# Sheet1.net
KiCad netlist of a schematic drawn in Altium Designer
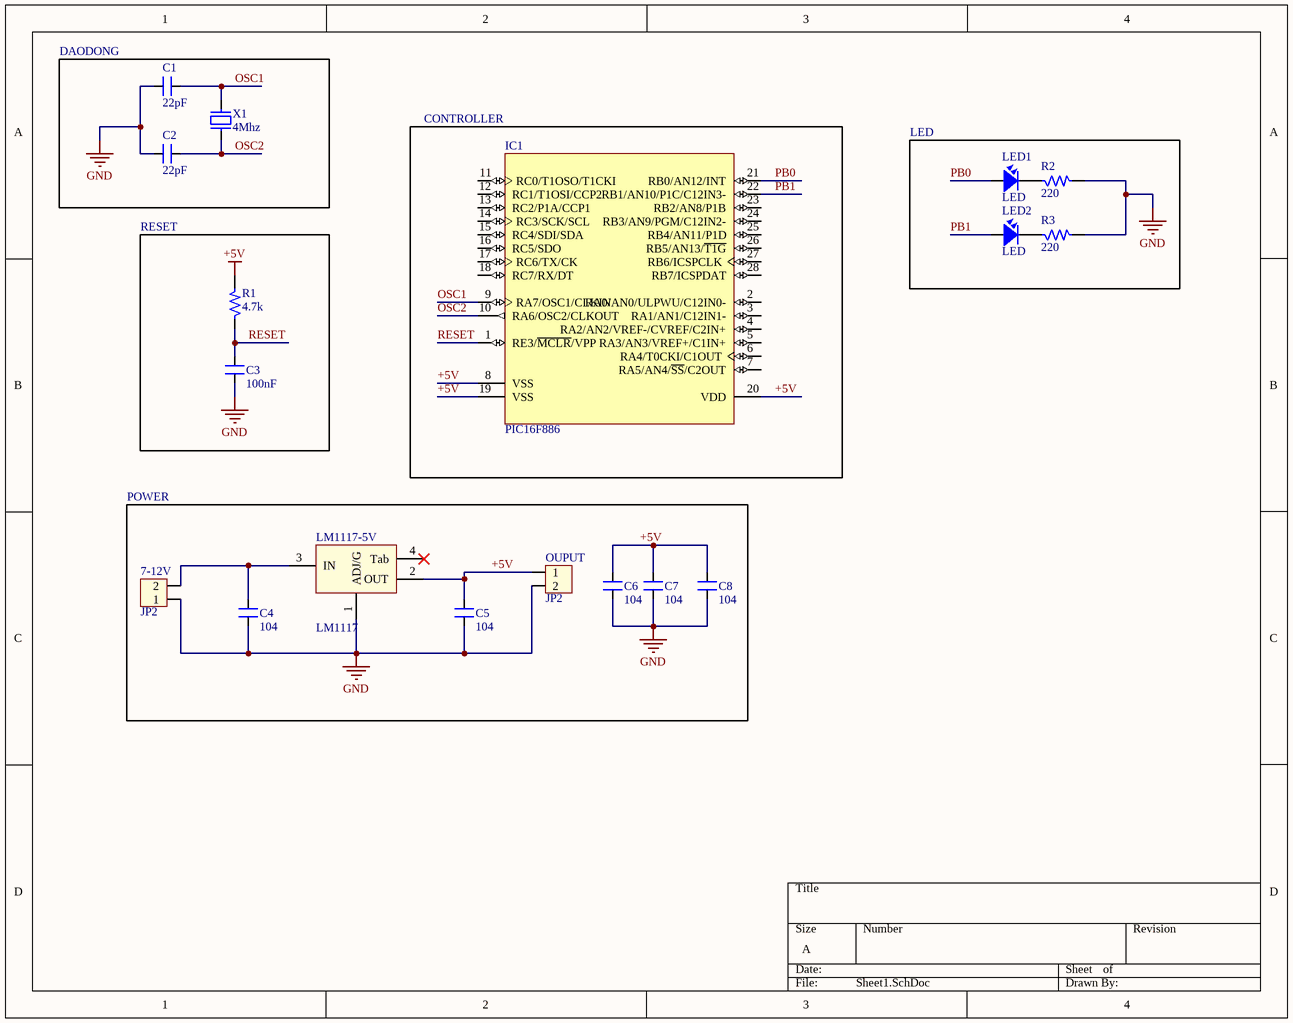
[diagram p0: Sheet1.SchDoc]

(export (version "E")
  (design (tool "Eeschema 10.0.6"))
  (components
    (comp (ref "7-12V")
      (value "JP2")
      (footprint "CON2")
      (description "Connector 2")
      (libsource (lib "syhaunguyen") (part "Con2"))
    )
    (comp (ref "C1")
      (value "22pF")
      (footprint "CN1")
      (description "Cap np  1pF - 472pF")
      (libsource (lib "syhaunguyen") (part "CN1"))
    )
    (comp (ref "C2")
      (value "22pF")
      (footprint "CN1")
      (description "Cap np  1pF - 472pF")
      (libsource (lib "syhaunguyen") (part "CN1"))
    )
    (comp (ref "C3")
      (value "100nF")
      (footprint "SM-0805")
      (description "Cap SMD")
      (libsource (lib "syhaunguyen") (part "CM"))
    )
    (comp (ref "C4")
      (value "104")
      (footprint "SM-0805")
      (description "Cap SMD")
      (libsource (lib "syhaunguyen") (part "CM"))
    )
    (comp (ref "C5")
      (value "104")
      (footprint "SM-0805")
      (description "Cap SMD")
      (libsource (lib "syhaunguyen") (part "CM"))
    )
    (comp (ref "C6")
      (value "104")
      (footprint "CN4")
      (description "Cap np W0.4")
      (libsource (lib "syhaunguyen") (part "CN4"))
    )
    (comp (ref "C7")
      (value "104")
      (footprint "CN4")
      (description "Cap np W0.4")
      (libsource (lib "syhaunguyen") (part "CN4"))
    )
    (comp (ref "C8")
      (value "104")
      (footprint "CN4")
      (description "Cap np W0.4")
      (libsource (lib "syhaunguyen") (part "CN4"))
    )
    (comp (ref "IC1")
      (value "PIC16F886")
      (footprint "DIP28/W0.3")
      (libsource (lib "syhaunguyen") (part "PIC16F886"))
    )
    (comp (ref "LED1")
      (value "LED")
      (footprint "LED-3")
      (description "LED Single colour Green and Red")
      (libsource (lib "syhaunguyen") (part "LED"))
    )
    (comp (ref "LED2")
      (value "LED")
      (footprint "LED-3")
      (description "LED Single colour Green and Red")
      (libsource (lib "syhaunguyen") (part "LED"))
    )
    (comp (ref "LM1117-5V")
      (value "LM1117")
      (footprint "SOT223-4N")
      (description "3v3")
      (libsource (lib "syhaunguyen") (part "LM1117"))
    )
    (comp (ref "OUPUT")
      (value "JP2")
      (footprint "CON2")
      (description "Connector 2")
      (libsource (lib "") (part "Con2_1"))
    )
    (comp (ref "R1")
      (value "4.7k")
      (footprint "R1/4W")
      (description "Resistor 1/4W")
      (libsource (lib "syhaunguyen") (part "R"))
    )
    (comp (ref "R2")
      (value "220")
      (footprint "R1/4W")
      (description "Resistor 1/4W")
      (libsource (lib "syhaunguyen") (part "R"))
    )
    (comp (ref "R3")
      (value "220")
      (footprint "R1/4W")
      (description "Resistor 1/4W")
      (libsource (lib "syhaunguyen") (part "R"))
    )
    (comp (ref "X1")
      (value "4Mhz")
      (footprint "XT2")
      (description "Crystal For all Crystal 2pin.")
      (libsource (lib "syhaunguyen") (part "XT2"))
    )
  )
  (nets
    (net (code "1") (name "+5V") (class "Default")
      (node (ref "C5") (pin "2") (pinfunction "2_2") (pintype "passive"))
      (node (ref "C6") (pin "2") (pinfunction "2_2") (pintype "passive"))
      (node (ref "C7") (pin "2") (pinfunction "2_2") (pintype "passive"))
      (node (ref "C8") (pin "2") (pinfunction "2_2") (pintype "passive"))
      (node (ref "IC1") (pin "19") (pinfunction "VSS_19") (pintype "power_in"))
      (node (ref "IC1") (pin "20") (pinfunction "VDD_20") (pintype "power_in"))
      (node (ref "IC1") (pin "8") (pinfunction "VSS_8") (pintype "power_in"))
      (node (ref "LM1117-5V") (pin "2") (pinfunction "OUT_2") (pintype "passive"))
      (node (ref "OUPUT") (pin "1") (pinfunction "1_1") (pintype "passive"))
      (node (ref "R1") (pin "2") (pinfunction "2_2") (pintype "passive"))
    )
    (net (code "2") (name "/OSC1") (class "Default")
      (node (ref "C1") (pin "2") (pinfunction "2_2") (pintype "passive"))
      (node (ref "IC1") (pin "9") (pinfunction "RA7/OSC1/CLKIN_9") (pintype "bidirectional"))
      (node (ref "X1") (pin "1") (pinfunction "1_1") (pintype "passive"))
    )
    (net (code "3") (name "/OSC2") (class "Default")
      (node (ref "C2") (pin "2") (pinfunction "2_2") (pintype "passive"))
      (node (ref "IC1") (pin "10") (pinfunction "RA6/OSC2/CLKOUT_10") (pintype "output"))
      (node (ref "X1") (pin "2") (pinfunction "2_2") (pintype "passive"))
    )
    (net (code "4") (name "/PB0") (class "Default")
      (node (ref "IC1") (pin "21") (pinfunction "RB0/AN12/INT_21") (pintype "bidirectional"))
      (node (ref "LED1") (pin "1") (pinfunction "1_1") (pintype "passive"))
    )
    (net (code "5") (name "/PB1") (class "Default")
      (node (ref "IC1") (pin "22") (pinfunction "RB1/AN10/P1C/C12IN3-_22") (pintype "bidirectional"))
      (node (ref "LED2") (pin "1") (pinfunction "1_1") (pintype "passive"))
    )
    (net (code "6") (name "/RESET") (class "Default")
      (node (ref "C3") (pin "2") (pinfunction "2_2") (pintype "passive"))
      (node (ref "IC1") (pin "1") (pinfunction "RE3/~{MCLR}/VPP_1") (pintype "bidirectional"))
      (node (ref "R1") (pin "1") (pinfunction "1_1") (pintype "passive"))
    )
    (net (code "7") (name "GND") (class "Default")
      (node (ref "7-12V") (pin "1") (pinfunction "1_1") (pintype "passive"))
      (node (ref "C1") (pin "1") (pinfunction "1_1") (pintype "passive"))
      (node (ref "C2") (pin "1") (pinfunction "1_1") (pintype "passive"))
      (node (ref "C3") (pin "1") (pinfunction "1_1") (pintype "passive"))
      (node (ref "C4") (pin "1") (pinfunction "1_1") (pintype "passive"))
      (node (ref "C5") (pin "1") (pinfunction "1_1") (pintype "passive"))
      (node (ref "C6") (pin "1") (pinfunction "1_1") (pintype "passive"))
      (node (ref "C7") (pin "1") (pinfunction "1_1") (pintype "passive"))
      (node (ref "C8") (pin "1") (pinfunction "1_1") (pintype "passive"))
      (node (ref "LM1117-5V") (pin "1") (pinfunction "ADJ/G_1") (pintype "passive"))
      (node (ref "OUPUT") (pin "2") (pinfunction "2_2") (pintype "passive"))
      (node (ref "R2") (pin "2") (pinfunction "2_2") (pintype "passive"))
      (node (ref "R3") (pin "2") (pinfunction "2_2") (pintype "passive"))
    )
    (net (code "8") (name "Net-(LED1-Pad2)") (class "Default")
      (node (ref "LED1") (pin "2") (pinfunction "2_2") (pintype "passive"))
      (node (ref "R2") (pin "1") (pinfunction "1_1") (pintype "passive"))
    )
    (net (code "9") (name "Net-(LED2-Pad2)") (class "Default")
      (node (ref "LED2") (pin "2") (pinfunction "2_2") (pintype "passive"))
      (node (ref "R3") (pin "1") (pinfunction "1_1") (pintype "passive"))
    )
    (net (code "10") (name "Net-(LM1117-5V-IN)") (class "Default")
      (node (ref "7-12V") (pin "2") (pinfunction "2_2") (pintype "passive"))
      (node (ref "C4") (pin "2") (pinfunction "2_2") (pintype "passive"))
      (node (ref "LM1117-5V") (pin "3") (pinfunction "IN_3") (pintype "passive"))
    )
    (net (code "11") (name "unconnected-(IC1-RA0{slash}AN0{slash}ULPWU{slash}C12IN0--Pad2)") (class "Default")
      (node (ref "IC1") (pin "2") (pinfunction "RA0/AN0/ULPWU/C12IN0-_2") (pintype "bidirectional"))
    )
    (net (code "12") (name "unconnected-(IC1-RA1{slash}AN1{slash}C12IN1--Pad3)") (class "Default")
      (node (ref "IC1") (pin "3") (pinfunction "RA1/AN1/C12IN1-_3") (pintype "bidirectional"))
    )
    (net (code "13") (name "unconnected-(IC1-RA2{slash}AN2{slash}VREF-{slash}CVREF{slash}C2IN+-Pad4)") (class "Default")
      (node (ref "IC1") (pin "4") (pinfunction "RA2/AN2/VREF-/CVREF/C2IN+_4") (pintype "bidirectional"))
    )
    (net (code "14") (name "unconnected-(IC1-RA3{slash}AN3{slash}VREF+{slash}C1IN+-Pad5)") (class "Default")
      (node (ref "IC1") (pin "5") (pinfunction "RA3/AN3/VREF+/C1IN+_5") (pintype "bidirectional"))
    )
    (net (code "15") (name "unconnected-(IC1-RA4{slash}T0CKI{slash}C1OUT-Pad6)") (class "Default")
      (node (ref "IC1") (pin "6") (pinfunction "RA4/T0CKI/C1OUT_6") (pintype "bidirectional"))
    )
    (net (code "16") (name "unconnected-(IC1-RA5{slash}AN4{slash}~{SS}{slash}C2OUT-Pad7)") (class "Default")
      (node (ref "IC1") (pin "7") (pinfunction "RA5/AN4/~{SS}/C2OUT_7") (pintype "bidirectional"))
    )
    (net (code "17") (name "unconnected-(IC1-RB2{slash}AN8{slash}P1B-Pad23)") (class "Default")
      (node (ref "IC1") (pin "23") (pinfunction "RB2/AN8/P1B_23") (pintype "bidirectional"))
    )
    (net (code "18") (name "unconnected-(IC1-RB3{slash}AN9{slash}PGM{slash}C12IN2--Pad24)") (class "Default")
      (node (ref "IC1") (pin "24") (pinfunction "RB3/AN9/PGM/C12IN2-_24") (pintype "bidirectional"))
    )
    (net (code "19") (name "unconnected-(IC1-RB4{slash}AN11{slash}P1D-Pad25)") (class "Default")
      (node (ref "IC1") (pin "25") (pinfunction "RB4/AN11/P1D_25") (pintype "bidirectional"))
    )
    (net (code "20") (name "unconnected-(IC1-RB5{slash}AN13{slash}~{T1G}-Pad26)") (class "Default")
      (node (ref "IC1") (pin "26") (pinfunction "RB5/AN13/~{T1G}_26") (pintype "bidirectional"))
    )
    (net (code "21") (name "unconnected-(IC1-RB6{slash}ICSPCLK-Pad27)") (class "Default")
      (node (ref "IC1") (pin "27") (pinfunction "RB6/ICSPCLK_27") (pintype "bidirectional"))
    )
    (net (code "22") (name "unconnected-(IC1-RB7{slash}ICSPDAT-Pad28)") (class "Default")
      (node (ref "IC1") (pin "28") (pinfunction "RB7/ICSPDAT_28") (pintype "bidirectional"))
    )
    (net (code "23") (name "unconnected-(IC1-RC0{slash}T1OSO{slash}T1CKI-Pad11)") (class "Default")
      (node (ref "IC1") (pin "11") (pinfunction "RC0/T1OSO/T1CKI_11") (pintype "bidirectional"))
    )
    (net (code "24") (name "unconnected-(IC1-RC1{slash}T1OSI{slash}CCP2-Pad12)") (class "Default")
      (node (ref "IC1") (pin "12") (pinfunction "RC1/T1OSI/CCP2_12") (pintype "bidirectional"))
    )
    (net (code "25") (name "unconnected-(IC1-RC2{slash}P1A{slash}CCP1-Pad13)") (class "Default")
      (node (ref "IC1") (pin "13") (pinfunction "RC2/P1A/CCP1_13") (pintype "bidirectional"))
    )
    (net (code "26") (name "unconnected-(IC1-RC3{slash}SCK{slash}SCL-Pad14)") (class "Default")
      (node (ref "IC1") (pin "14") (pinfunction "RC3/SCK/SCL_14") (pintype "bidirectional"))
    )
    (net (code "27") (name "unconnected-(IC1-RC4{slash}SDI{slash}SDA-Pad15)") (class "Default")
      (node (ref "IC1") (pin "15") (pinfunction "RC4/SDI/SDA_15") (pintype "bidirectional"))
    )
    (net (code "28") (name "unconnected-(IC1-RC5{slash}SDO-Pad16)") (class "Default")
      (node (ref "IC1") (pin "16") (pinfunction "RC5/SDO_16") (pintype "bidirectional"))
    )
    (net (code "29") (name "unconnected-(IC1-RC6{slash}TX{slash}CK-Pad17)") (class "Default")
      (node (ref "IC1") (pin "17") (pinfunction "RC6/TX/CK_17") (pintype "bidirectional"))
    )
    (net (code "30") (name "unconnected-(IC1-RC7{slash}RX{slash}DT-Pad18)") (class "Default")
      (node (ref "IC1") (pin "18") (pinfunction "RC7/RX/DT_18") (pintype "bidirectional"))
    )
    (net (code "31") (name "unconnected-(LM1117-5V-Tab-Pad4)") (class "Default")
      (node (ref "LM1117-5V") (pin "4") (pinfunction "Tab_4") (pintype "passive+no_connect"))
    )
  )
)
